# input_vhall.net
KiCad netlist of a schematic drawn in Altium Designer
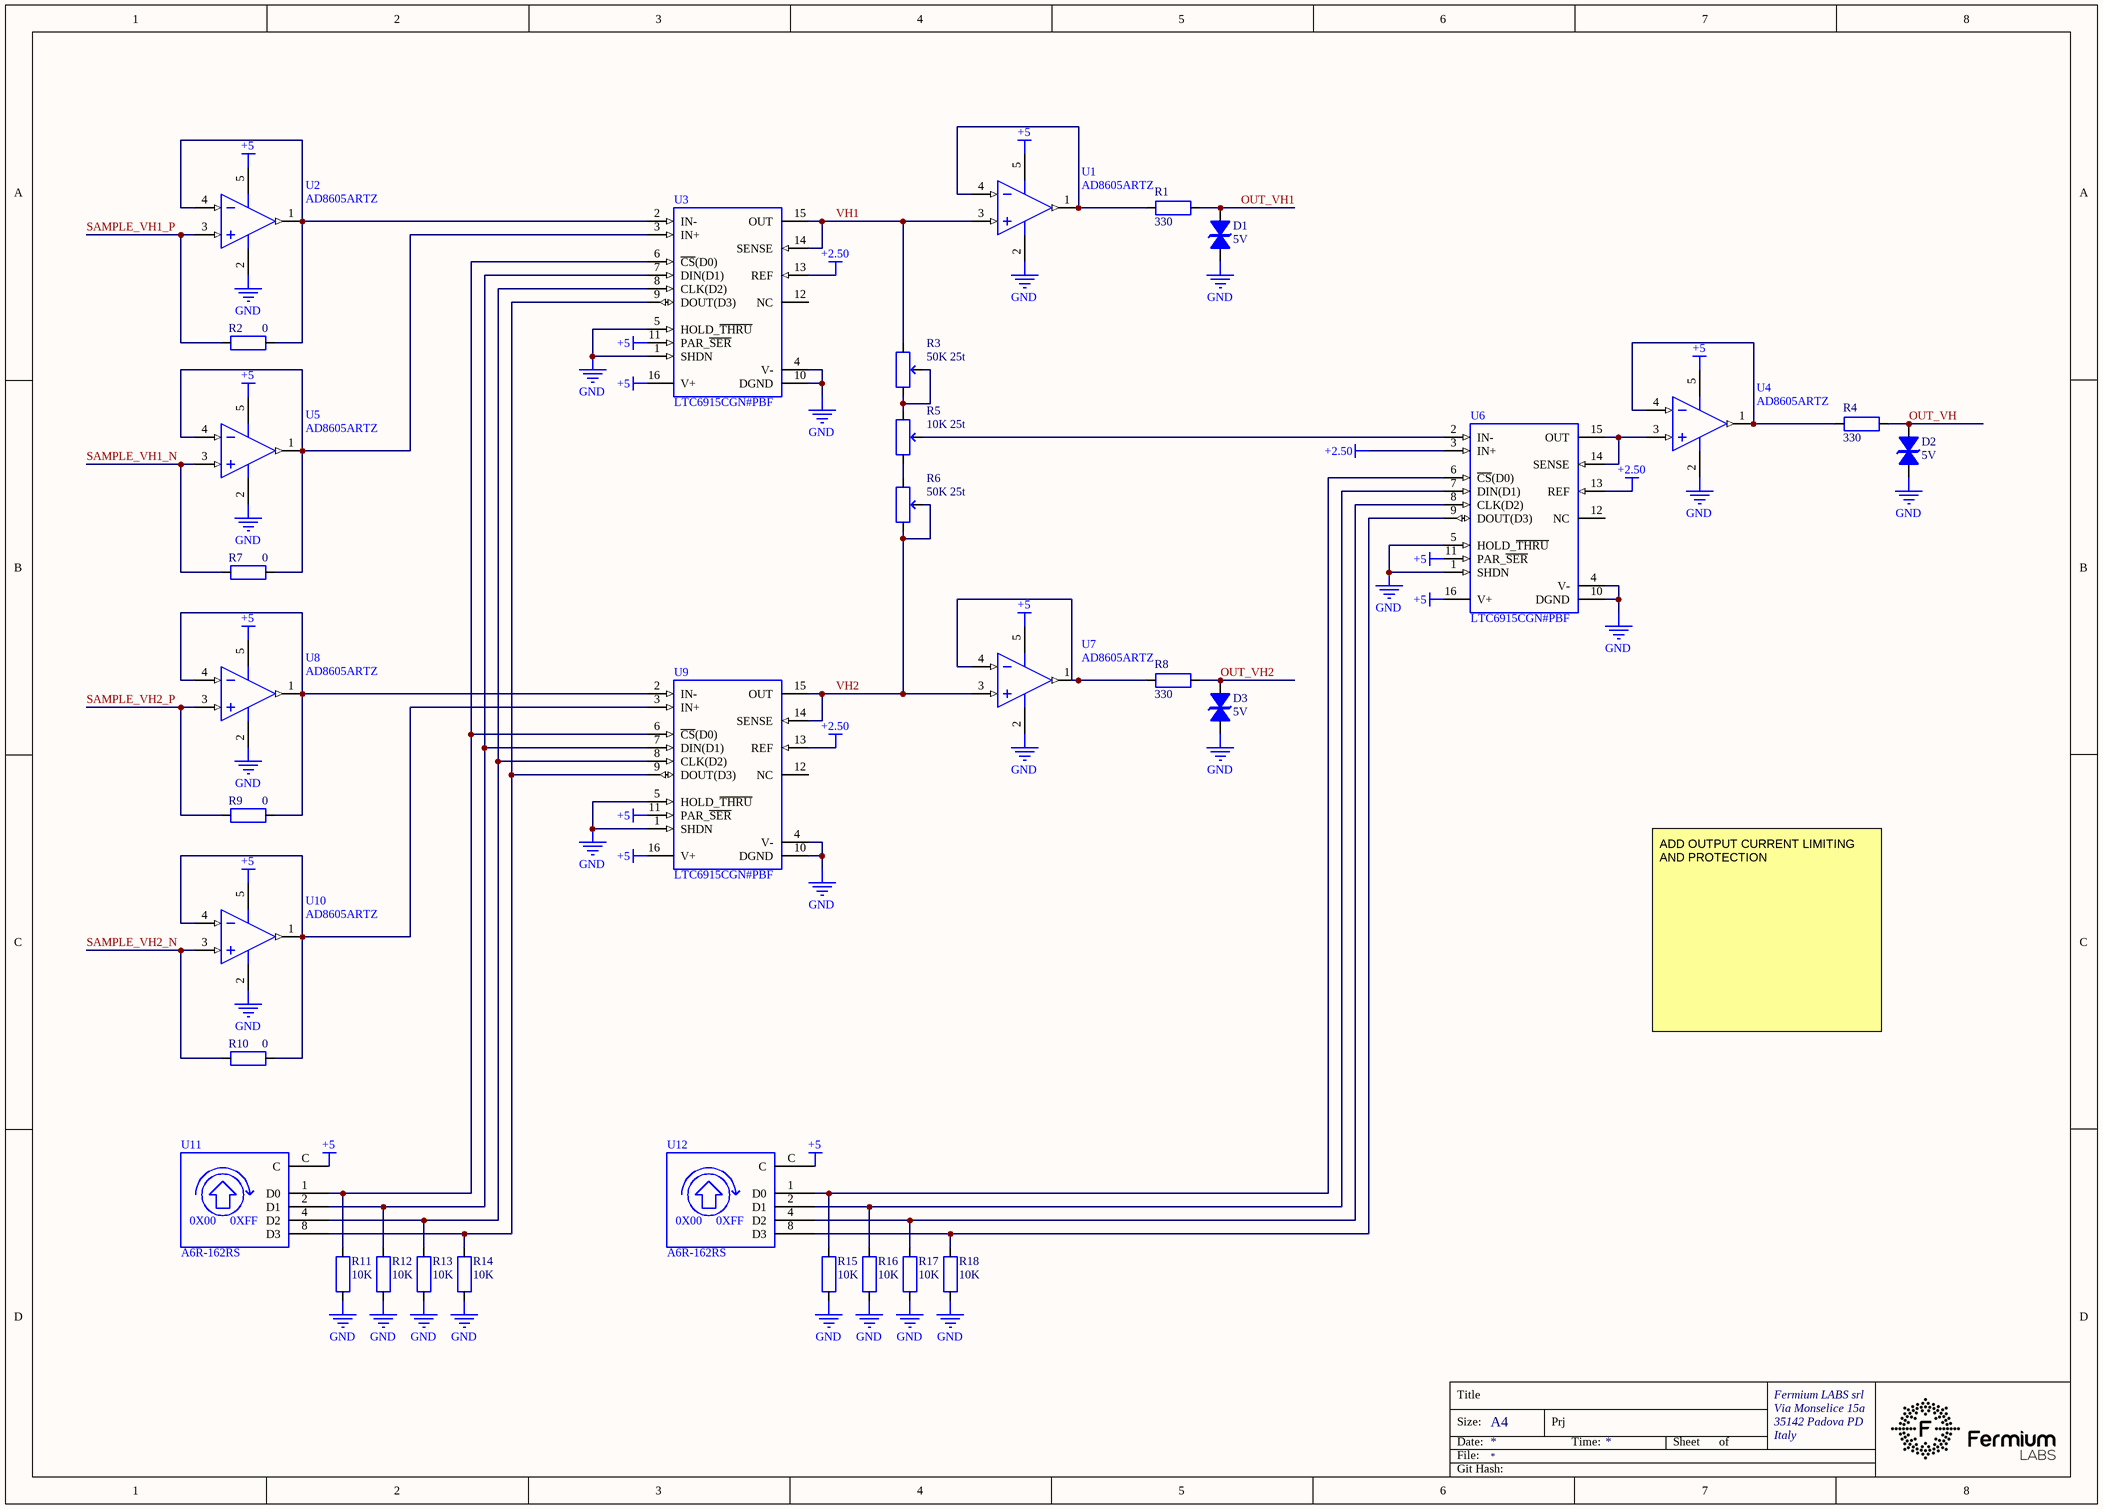
[diagram p0: input_vhall.SchDoc]

(export (version "E")
  (design (tool "Eeschema 10.0.6"))
  (components
    (comp (ref "D1")
      (value "5V")
      (footprint "SOD523F")
      (description "DIODE SMD TVS 5V BIDIRECTIONAL SOD-523")
      (fields (field (name "PART NUMBER") "daa58212-38e2-4326-a156-8e48058c46f1"))
      (libsource (lib "frmdblib") (part "GENERIC_D_TVS_BI"))
    )
    (comp (ref "D2")
      (value "5V")
      (footprint "SOD523F")
      (description "DIODE SMD TVS 5V BIDIRECTIONAL SOD-523")
      (fields (field (name "PART NUMBER") "daa58212-38e2-4326-a156-8e48058c46f1"))
      (libsource (lib "frmdblib") (part "GENERIC_D_TVS_BI"))
    )
    (comp (ref "D3")
      (value "5V")
      (footprint "SOD523F")
      (description "DIODE SMD TVS 5V BIDIRECTIONAL SOD-523")
      (fields (field (name "PART NUMBER") "daa58212-38e2-4326-a156-8e48058c46f1"))
      (libsource (lib "frmdblib") (part "GENERIC_D_TVS_BI"))
    )
    (comp (ref "R1")
      (value "330")
      (description "RES SMD 330 OHM 1% 1/10W 0603")
      (fields (field (name "PART NUMBER") "e8555d7b-eeda-4727-b2e1-550cdc03d819"))
      (libsource (lib "frmdblib") (part "GENERIC_R"))
    )
    (comp (ref "R2")
      (value "0")
      (footprint "RES 0603_1608")
      (description "RES SMD 0 OHM 5% 1/10W 0603")
      (fields (field (name "PART NUMBER") "6ae227f9-847f-4766-8522-e11a83531204"))
      (libsource (lib "frmdblib") (part "GENERIC_R"))
    )
    (comp (ref "R3")
      (value "50K 25t")
      (footprint "F9540903-09ED-4909-856A-DED10E64451E")
      (description "POT TRIMMER LINEAR 50K 25TURNS VERT THT")
      (fields (field (name "PART NUMBER") "90164141-8820-4471-9a6f-9a984ce9068c"))
      (libsource (lib "frmdblib") (part "GENERIC_R_VAR"))
    )
    (comp (ref "R4")
      (value "330")
      (description "RES SMD 330 OHM 1% 1/10W 0603")
      (fields (field (name "PART NUMBER") "e8555d7b-eeda-4727-b2e1-550cdc03d819"))
      (libsource (lib "frmdblib") (part "GENERIC_R"))
    )
    (comp (ref "R5")
      (value "10K 25t")
      (footprint "F9540903-09ED-4909-856A-DED10E64451E")
      (description "POT TRIMMER LINEAR 10K 25TURNS VERT THT")
      (fields (field (name "PART NUMBER") "613f65ed-4d8d-44d0-9fe5-67eff78392c9"))
      (libsource (lib "frmdblib") (part "GENERIC_R_VAR"))
    )
    (comp (ref "R6")
      (value "50K 25t")
      (footprint "F9540903-09ED-4909-856A-DED10E64451E")
      (description "POT TRIMMER LINEAR 50K 25TURNS VERT THT")
      (fields (field (name "PART NUMBER") "90164141-8820-4471-9a6f-9a984ce9068c"))
      (libsource (lib "frmdblib") (part "GENERIC_R_VAR"))
    )
    (comp (ref "R7")
      (value "0")
      (footprint "RES 0603_1608")
      (description "RES SMD 0 OHM 5% 1/10W 0603")
      (fields (field (name "PART NUMBER") "6ae227f9-847f-4766-8522-e11a83531204"))
      (libsource (lib "frmdblib") (part "GENERIC_R"))
    )
    (comp (ref "R8")
      (value "330")
      (description "RES SMD 330 OHM 1% 1/10W 0603")
      (fields (field (name "PART NUMBER") "e8555d7b-eeda-4727-b2e1-550cdc03d819"))
      (libsource (lib "frmdblib") (part "GENERIC_R"))
    )
    (comp (ref "R9")
      (value "0")
      (footprint "RES 0603_1608")
      (description "RES SMD 0 OHM 5% 1/10W 0603")
      (fields (field (name "PART NUMBER") "6ae227f9-847f-4766-8522-e11a83531204"))
      (libsource (lib "frmdblib") (part "GENERIC_R"))
    )
    (comp (ref "R10")
      (value "0")
      (footprint "RES 0603_1608")
      (description "RES SMD 0 OHM 5% 1/10W 0603")
      (fields (field (name "PART NUMBER") "6ae227f9-847f-4766-8522-e11a83531204"))
      (libsource (lib "frmdblib") (part "GENERIC_R"))
    )
    (comp (ref "R11")
      (value "10K")
      (footprint "RES 0603_1608")
      (description "RES SMD 10K OHM 1% 1/10W 0603")
      (fields (field (name "PART NUMBER") "93242766-ba1d-462d-b58f-ce1dfc4129c8"))
      (libsource (lib "frmdblib") (part "GENERIC_R"))
    )
    (comp (ref "R12")
      (value "10K")
      (footprint "RES 0603_1608")
      (description "RES SMD 10K OHM 1% 1/10W 0603")
      (fields (field (name "PART NUMBER") "93242766-ba1d-462d-b58f-ce1dfc4129c8"))
      (libsource (lib "frmdblib") (part "GENERIC_R"))
    )
    (comp (ref "R13")
      (value "10K")
      (footprint "RES 0603_1608")
      (description "RES SMD 10K OHM 1% 1/10W 0603")
      (fields (field (name "PART NUMBER") "93242766-ba1d-462d-b58f-ce1dfc4129c8"))
      (libsource (lib "frmdblib") (part "GENERIC_R"))
    )
    (comp (ref "R14")
      (value "10K")
      (footprint "RES 0603_1608")
      (description "RES SMD 10K OHM 1% 1/10W 0603")
      (fields (field (name "PART NUMBER") "93242766-ba1d-462d-b58f-ce1dfc4129c8"))
      (libsource (lib "frmdblib") (part "GENERIC_R"))
    )
    (comp (ref "R15")
      (value "10K")
      (footprint "RES 0603_1608")
      (description "RES SMD 10K OHM 1% 1/10W 0603")
      (fields (field (name "PART NUMBER") "93242766-ba1d-462d-b58f-ce1dfc4129c8"))
      (libsource (lib "frmdblib") (part "GENERIC_R"))
    )
    (comp (ref "R16")
      (value "10K")
      (footprint "RES 0603_1608")
      (description "RES SMD 10K OHM 1% 1/10W 0603")
      (fields (field (name "PART NUMBER") "93242766-ba1d-462d-b58f-ce1dfc4129c8"))
      (libsource (lib "frmdblib") (part "GENERIC_R"))
    )
    (comp (ref "R17")
      (value "10K")
      (footprint "RES 0603_1608")
      (description "RES SMD 10K OHM 1% 1/10W 0603")
      (fields (field (name "PART NUMBER") "93242766-ba1d-462d-b58f-ce1dfc4129c8"))
      (libsource (lib "frmdblib") (part "GENERIC_R"))
    )
    (comp (ref "R18")
      (value "10K")
      (footprint "RES 0603_1608")
      (description "RES SMD 10K OHM 1% 1/10W 0603")
      (fields (field (name "PART NUMBER") "93242766-ba1d-462d-b58f-ce1dfc4129c8"))
      (libsource (lib "frmdblib") (part "GENERIC_R"))
    )
    (comp (ref "U1")
      (value "AD8605ARTZ")
      (footprint "A3DDA0BC-073E-4B18-9613-F713A7EC1E27")
      (description "IC OPAMP 65uV 1pA RRIO 5V 80mA SOT-23-5")
      (fields (field (name "PART NUMBER") "5610e9ea-bca8-49b2-8e5f-11409231f6a4"))
      (libsource (lib "frmdblib") (part "8096D751-9DCE-401B-B65E-AAEE0733EA70"))
    )
    (comp (ref "U2")
      (value "AD8605ARTZ")
      (footprint "A3DDA0BC-073E-4B18-9613-F713A7EC1E27")
      (description "IC OPAMP 65uV 1pA RRIO 5V 80mA SOT-23-5")
      (fields (field (name "PART NUMBER") "5610e9ea-bca8-49b2-8e5f-11409231f6a4"))
      (libsource (lib "frmdblib") (part "8096D751-9DCE-401B-B65E-AAEE0733EA70"))
    )
    (comp (ref "U3")
      (value "LTC6915CGN#PBF")
      (footprint "517EE8A2-9FD8-4174-996D-BDBF76CA3EEB")
      (description "IC PGA G0-4094 SPI-PARALLEL 5V RRIO SSOP-16")
      (fields (field (name "PART NUMBER") "59fe82cd-fd18-4813-9f52-e2e78a460aff"))
      (libsource (lib "frmdblib") (part "092C41BF-C4B2-4D13-B4E9-531E546592A0"))
    )
    (comp (ref "U4")
      (value "AD8605ARTZ")
      (footprint "A3DDA0BC-073E-4B18-9613-F713A7EC1E27")
      (description "IC OPAMP 65uV 1pA RRIO 5V 80mA SOT-23-5")
      (fields (field (name "PART NUMBER") "5610e9ea-bca8-49b2-8e5f-11409231f6a4"))
      (libsource (lib "frmdblib") (part "8096D751-9DCE-401B-B65E-AAEE0733EA70"))
    )
    (comp (ref "U5")
      (value "AD8605ARTZ")
      (footprint "A3DDA0BC-073E-4B18-9613-F713A7EC1E27")
      (description "IC OPAMP 65uV 1pA RRIO 5V 80mA SOT-23-5")
      (fields (field (name "PART NUMBER") "5610e9ea-bca8-49b2-8e5f-11409231f6a4"))
      (libsource (lib "frmdblib") (part "8096D751-9DCE-401B-B65E-AAEE0733EA70"))
    )
    (comp (ref "U6")
      (value "LTC6915CGN#PBF")
      (footprint "517EE8A2-9FD8-4174-996D-BDBF76CA3EEB")
      (description "IC PGA G0-4094 SPI-PARALLEL 5V RRIO SSOP-16")
      (fields (field (name "PART NUMBER") "59fe82cd-fd18-4813-9f52-e2e78a460aff"))
      (libsource (lib "frmdblib") (part "092C41BF-C4B2-4D13-B4E9-531E546592A0"))
    )
    (comp (ref "U7")
      (value "AD8605ARTZ")
      (footprint "A3DDA0BC-073E-4B18-9613-F713A7EC1E27")
      (description "IC OPAMP 65uV 1pA RRIO 5V 80mA SOT-23-5")
      (fields (field (name "PART NUMBER") "5610e9ea-bca8-49b2-8e5f-11409231f6a4"))
      (libsource (lib "frmdblib") (part "8096D751-9DCE-401B-B65E-AAEE0733EA70"))
    )
    (comp (ref "U8")
      (value "AD8605ARTZ")
      (footprint "A3DDA0BC-073E-4B18-9613-F713A7EC1E27")
      (description "IC OPAMP 65uV 1pA RRIO 5V 80mA SOT-23-5")
      (fields (field (name "PART NUMBER") "5610e9ea-bca8-49b2-8e5f-11409231f6a4"))
      (libsource (lib "frmdblib") (part "8096D751-9DCE-401B-B65E-AAEE0733EA70"))
    )
    (comp (ref "U9")
      (value "LTC6915CGN#PBF")
      (footprint "517EE8A2-9FD8-4174-996D-BDBF76CA3EEB")
      (description "IC PGA G0-4094 SPI-PARALLEL 5V RRIO SSOP-16")
      (fields (field (name "PART NUMBER") "59fe82cd-fd18-4813-9f52-e2e78a460aff"))
      (libsource (lib "frmdblib") (part "092C41BF-C4B2-4D13-B4E9-531E546592A0"))
    )
    (comp (ref "U10")
      (value "AD8605ARTZ")
      (footprint "A3DDA0BC-073E-4B18-9613-F713A7EC1E27")
      (description "IC OPAMP 65uV 1pA RRIO 5V 80mA SOT-23-5")
      (fields (field (name "PART NUMBER") "5610e9ea-bca8-49b2-8e5f-11409231f6a4"))
      (libsource (lib "frmdblib") (part "8096D751-9DCE-401B-B65E-AAEE0733EA70"))
    )
    (comp (ref "U11")
      (value "A6R-162RS")
      (footprint "2599C238-5645-4A8C-8BF9-C7515FACCFA0")
      (description "SWITCH ROTARY HEX/BCD 16 POSITIONS")
      (fields (field (name "PART NUMBER") "bbf157ad-cd7a-4e82-97e3-d6a037590888"))
      (libsource (lib "frmdblib") (part "EFC705A0-D700-486A-81AB-6EE045EE6C24"))
    )
    (comp (ref "U12")
      (value "A6R-162RS")
      (footprint "2599C238-5645-4A8C-8BF9-C7515FACCFA0")
      (description "SWITCH ROTARY HEX/BCD 16 POSITIONS")
      (fields (field (name "PART NUMBER") "bbf157ad-cd7a-4e82-97e3-d6a037590888"))
      (libsource (lib "frmdblib") (part "EFC705A0-D700-486A-81AB-6EE045EE6C24"))
    )
  )
  (nets
    (net (code "1") (name "+2.50") (class "Default")
      (node (ref "U3") (pin "13") (pinfunction "REF_13") (pintype "input"))
      (node (ref "U6") (pin "13") (pinfunction "REF_13") (pintype "input"))
      (node (ref "U6") (pin "3") (pinfunction "IN+_3") (pintype "input"))
      (node (ref "U9") (pin "13") (pinfunction "REF_13") (pintype "input"))
    )
    (net (code "2") (name "+5") (class "Default")
      (node (ref "U1") (pin "5") (pinfunction "+V_5") (pintype "power_in"))
      (node (ref "U10") (pin "5") (pinfunction "+V_5") (pintype "power_in"))
      (node (ref "U11") (pin "C") (pinfunction "C_C") (pintype "passive"))
      (node (ref "U12") (pin "C") (pinfunction "C_C") (pintype "passive"))
      (node (ref "U2") (pin "5") (pinfunction "+V_5") (pintype "power_in"))
      (node (ref "U3") (pin "11") (pinfunction "PAR_~{SER}_11") (pintype "input"))
      (node (ref "U3") (pin "16") (pinfunction "V+_16") (pintype "power_in"))
      (node (ref "U4") (pin "5") (pinfunction "+V_5") (pintype "power_in"))
      (node (ref "U5") (pin "5") (pinfunction "+V_5") (pintype "power_in"))
      (node (ref "U6") (pin "11") (pinfunction "PAR_~{SER}_11") (pintype "input"))
      (node (ref "U6") (pin "16") (pinfunction "V+_16") (pintype "power_in"))
      (node (ref "U7") (pin "5") (pinfunction "+V_5") (pintype "power_in"))
      (node (ref "U8") (pin "5") (pinfunction "+V_5") (pintype "power_in"))
      (node (ref "U9") (pin "11") (pinfunction "PAR_~{SER}_11") (pintype "input"))
      (node (ref "U9") (pin "16") (pinfunction "V+_16") (pintype "power_in"))
    )
    (net (code "3") (name "/OUT_VH") (class "Default")
      (node (ref "D2") (pin "1") (pintype "passive"))
      (node (ref "R4") (pin "2") (pintype "passive"))
    )
    (net (code "4") (name "/OUT_VH1") (class "Default")
      (node (ref "D1") (pin "1") (pintype "passive"))
      (node (ref "R1") (pin "2") (pintype "passive"))
    )
    (net (code "5") (name "/OUT_VH2") (class "Default")
      (node (ref "D3") (pin "1") (pintype "passive"))
      (node (ref "R8") (pin "2") (pintype "passive"))
    )
    (net (code "6") (name "/SAMPLE_VH1_N") (class "Default")
      (node (ref "R7") (pin "1") (pintype "passive"))
      (node (ref "U5") (pin "3") (pinfunction "+IN_3") (pintype "input"))
    )
    (net (code "7") (name "/SAMPLE_VH1_P") (class "Default")
      (node (ref "R2") (pin "1") (pintype "passive"))
      (node (ref "U2") (pin "3") (pinfunction "+IN_3") (pintype "input"))
    )
    (net (code "8") (name "/SAMPLE_VH2_N") (class "Default")
      (node (ref "R10") (pin "1") (pintype "passive"))
      (node (ref "U10") (pin "3") (pinfunction "+IN_3") (pintype "input"))
    )
    (net (code "9") (name "/SAMPLE_VH2_P") (class "Default")
      (node (ref "R9") (pin "1") (pintype "passive"))
      (node (ref "U8") (pin "3") (pinfunction "+IN_3") (pintype "input"))
    )
    (net (code "10") (name "/VH1") (class "Default")
      (node (ref "R3") (pin "1") (pintype "passive"))
      (node (ref "U1") (pin "3") (pinfunction "+IN_3") (pintype "input"))
      (node (ref "U3") (pin "14") (pinfunction "SENSE_14") (pintype "input"))
      (node (ref "U3") (pin "15") (pinfunction "OUT_15") (pintype "tri_state"))
    )
    (net (code "11") (name "/VH2") (class "Default")
      (node (ref "R6") (pin "2") (pintype "passive"))
      (node (ref "R6") (pin "3") (pintype "passive"))
      (node (ref "U7") (pin "3") (pinfunction "+IN_3") (pintype "input"))
      (node (ref "U9") (pin "14") (pinfunction "SENSE_14") (pintype "input"))
      (node (ref "U9") (pin "15") (pinfunction "OUT_15") (pintype "tri_state"))
    )
    (net (code "12") (name "GND") (class "Default")
      (node (ref "D1") (pin "2") (pintype "passive"))
      (node (ref "D2") (pin "2") (pintype "passive"))
      (node (ref "D3") (pin "2") (pintype "passive"))
      (node (ref "R11") (pin "1") (pintype "passive"))
      (node (ref "R12") (pin "1") (pintype "passive"))
      (node (ref "R13") (pin "1") (pintype "passive"))
      (node (ref "R14") (pin "1") (pintype "passive"))
      (node (ref "R15") (pin "1") (pintype "passive"))
      (node (ref "R16") (pin "1") (pintype "passive"))
      (node (ref "R17") (pin "1") (pintype "passive"))
      (node (ref "R18") (pin "1") (pintype "passive"))
      (node (ref "U1") (pin "2") (pinfunction "-V_2") (pintype "power_in"))
      (node (ref "U10") (pin "2") (pinfunction "-V_2") (pintype "power_in"))
      (node (ref "U2") (pin "2") (pinfunction "-V_2") (pintype "power_in"))
      (node (ref "U3") (pin "1") (pinfunction "SHDN_1") (pintype "input"))
      (node (ref "U3") (pin "10") (pinfunction "DGND_10") (pintype "power_in"))
      (node (ref "U3") (pin "4") (pinfunction "V-_4") (pintype "power_in"))
      (node (ref "U3") (pin "5") (pinfunction "HOLD_~{THRU}_5") (pintype "input"))
      (node (ref "U4") (pin "2") (pinfunction "-V_2") (pintype "power_in"))
      (node (ref "U5") (pin "2") (pinfunction "-V_2") (pintype "power_in"))
      (node (ref "U6") (pin "1") (pinfunction "SHDN_1") (pintype "input"))
      (node (ref "U6") (pin "10") (pinfunction "DGND_10") (pintype "power_in"))
      (node (ref "U6") (pin "4") (pinfunction "V-_4") (pintype "power_in"))
      (node (ref "U6") (pin "5") (pinfunction "HOLD_~{THRU}_5") (pintype "input"))
      (node (ref "U7") (pin "2") (pinfunction "-V_2") (pintype "power_in"))
      (node (ref "U8") (pin "2") (pinfunction "-V_2") (pintype "power_in"))
      (node (ref "U9") (pin "1") (pinfunction "SHDN_1") (pintype "input"))
      (node (ref "U9") (pin "10") (pinfunction "DGND_10") (pintype "power_in"))
      (node (ref "U9") (pin "4") (pinfunction "V-_4") (pintype "power_in"))
      (node (ref "U9") (pin "5") (pinfunction "HOLD_~{THRU}_5") (pintype "input"))
    )
    (net (code "13") (name "Net-(R3-Pad2)") (class "Default")
      (node (ref "R3") (pin "2") (pintype "passive"))
      (node (ref "R3") (pin "3") (pintype "passive"))
      (node (ref "R5") (pin "3") (pintype "passive"))
    )
    (net (code "14") (name "Net-(R5-Pad1)") (class "Default")
      (node (ref "R5") (pin "1") (pintype "passive"))
      (node (ref "R6") (pin "1") (pintype "passive"))
    )
    (net (code "15") (name "Net-(U1--IN)") (class "Default")
      (node (ref "R1") (pin "1") (pintype "passive"))
      (node (ref "U1") (pin "1") (pinfunction "OUT_1") (pintype "output"))
      (node (ref "U1") (pin "4") (pinfunction "-IN_4") (pintype "input"))
    )
    (net (code "16") (name "Net-(U2--IN)") (class "Default")
      (node (ref "R2") (pin "2") (pintype "passive"))
      (node (ref "U2") (pin "1") (pinfunction "OUT_1") (pintype "output"))
      (node (ref "U2") (pin "4") (pinfunction "-IN_4") (pintype "input"))
      (node (ref "U3") (pin "2") (pinfunction "IN-_2") (pintype "input"))
    )
    (net (code "17") (name "Net-(U3-IN+)") (class "Default")
      (node (ref "R7") (pin "2") (pintype "passive"))
      (node (ref "U3") (pin "3") (pinfunction "IN+_3") (pintype "input"))
      (node (ref "U5") (pin "1") (pinfunction "OUT_1") (pintype "output"))
      (node (ref "U5") (pin "4") (pinfunction "-IN_4") (pintype "input"))
    )
    (net (code "18") (name "Net-(U4-+IN)") (class "Default")
      (node (ref "U4") (pin "3") (pinfunction "+IN_3") (pintype "input"))
      (node (ref "U6") (pin "14") (pinfunction "SENSE_14") (pintype "input"))
      (node (ref "U6") (pin "15") (pinfunction "OUT_15") (pintype "tri_state"))
    )
    (net (code "19") (name "Net-(U4--IN)") (class "Default")
      (node (ref "R4") (pin "1") (pintype "passive"))
      (node (ref "U4") (pin "1") (pinfunction "OUT_1") (pintype "output"))
      (node (ref "U4") (pin "4") (pinfunction "-IN_4") (pintype "input"))
    )
    (net (code "20") (name "Net-(U6-IN-)") (class "Default")
      (node (ref "R5") (pin "2") (pintype "passive"))
      (node (ref "U6") (pin "2") (pinfunction "IN-_2") (pintype "input"))
    )
    (net (code "21") (name "Net-(U7--IN)") (class "Default")
      (node (ref "R8") (pin "1") (pintype "passive"))
      (node (ref "U7") (pin "1") (pinfunction "OUT_1") (pintype "output"))
      (node (ref "U7") (pin "4") (pinfunction "-IN_4") (pintype "input"))
    )
    (net (code "22") (name "Net-(U8--IN)") (class "Default")
      (node (ref "R9") (pin "2") (pintype "passive"))
      (node (ref "U8") (pin "1") (pinfunction "OUT_1") (pintype "output"))
      (node (ref "U8") (pin "4") (pinfunction "-IN_4") (pintype "input"))
      (node (ref "U9") (pin "2") (pinfunction "IN-_2") (pintype "input"))
    )
    (net (code "23") (name "Net-(U10--IN)") (class "Default")
      (node (ref "R10") (pin "2") (pintype "passive"))
      (node (ref "U10") (pin "1") (pinfunction "OUT_1") (pintype "output"))
      (node (ref "U10") (pin "4") (pinfunction "-IN_4") (pintype "input"))
      (node (ref "U9") (pin "3") (pinfunction "IN+_3") (pintype "input"))
    )
    (net (code "24") (name "Net-(U11-D0)") (class "Default")
      (node (ref "R11") (pin "2") (pintype "passive"))
      (node (ref "U11") (pin "1") (pinfunction "D0_1") (pintype "passive"))
      (node (ref "U3") (pin "6") (pinfunction "~{CS}(D0)_6") (pintype "input"))
      (node (ref "U9") (pin "6") (pinfunction "~{CS}(D0)_6") (pintype "input"))
    )
    (net (code "25") (name "Net-(U11-D1)") (class "Default")
      (node (ref "R12") (pin "2") (pintype "passive"))
      (node (ref "U11") (pin "2") (pinfunction "D1_2") (pintype "passive"))
      (node (ref "U3") (pin "7") (pinfunction "DIN(D1)_7") (pintype "input"))
      (node (ref "U9") (pin "7") (pinfunction "DIN(D1)_7") (pintype "input"))
    )
    (net (code "26") (name "Net-(U11-D2)") (class "Default")
      (node (ref "R13") (pin "2") (pintype "passive"))
      (node (ref "U11") (pin "4") (pinfunction "D2_4") (pintype "passive"))
      (node (ref "U3") (pin "8") (pinfunction "CLK(D2)_8") (pintype "input"))
      (node (ref "U9") (pin "8") (pinfunction "CLK(D2)_8") (pintype "input"))
    )
    (net (code "27") (name "Net-(U11-D3)") (class "Default")
      (node (ref "R14") (pin "2") (pintype "passive"))
      (node (ref "U11") (pin "8") (pinfunction "D3_8") (pintype "passive"))
      (node (ref "U3") (pin "9") (pinfunction "DOUT(D3)_9") (pintype "bidirectional"))
      (node (ref "U9") (pin "9") (pinfunction "DOUT(D3)_9") (pintype "bidirectional"))
    )
    (net (code "28") (name "Net-(U12-D0)") (class "Default")
      (node (ref "R15") (pin "2") (pintype "passive"))
      (node (ref "U12") (pin "1") (pinfunction "D0_1") (pintype "passive"))
      (node (ref "U6") (pin "6") (pinfunction "~{CS}(D0)_6") (pintype "input"))
    )
    (net (code "29") (name "Net-(U12-D1)") (class "Default")
      (node (ref "R16") (pin "2") (pintype "passive"))
      (node (ref "U12") (pin "2") (pinfunction "D1_2") (pintype "passive"))
      (node (ref "U6") (pin "7") (pinfunction "DIN(D1)_7") (pintype "input"))
    )
    (net (code "30") (name "Net-(U12-D2)") (class "Default")
      (node (ref "R17") (pin "2") (pintype "passive"))
      (node (ref "U12") (pin "4") (pinfunction "D2_4") (pintype "passive"))
      (node (ref "U6") (pin "8") (pinfunction "CLK(D2)_8") (pintype "input"))
    )
    (net (code "31") (name "Net-(U12-D3)") (class "Default")
      (node (ref "R18") (pin "2") (pintype "passive"))
      (node (ref "U12") (pin "8") (pinfunction "D3_8") (pintype "passive"))
      (node (ref "U6") (pin "9") (pinfunction "DOUT(D3)_9") (pintype "bidirectional"))
    )
    (net (code "32") (name "unconnected-(U3-NC-Pad12)") (class "Default")
      (node (ref "U3") (pin "12") (pinfunction "NC_12") (pintype "passive"))
    )
    (net (code "33") (name "unconnected-(U6-NC-Pad12)") (class "Default")
      (node (ref "U6") (pin "12") (pinfunction "NC_12") (pintype "passive"))
    )
    (net (code "34") (name "unconnected-(U9-NC-Pad12)") (class "Default")
      (node (ref "U9") (pin "12") (pinfunction "NC_12") (pintype "passive"))
    )
  )
)
